# EEPROM.net
KiCad netlist of a schematic drawn in Altium Designer
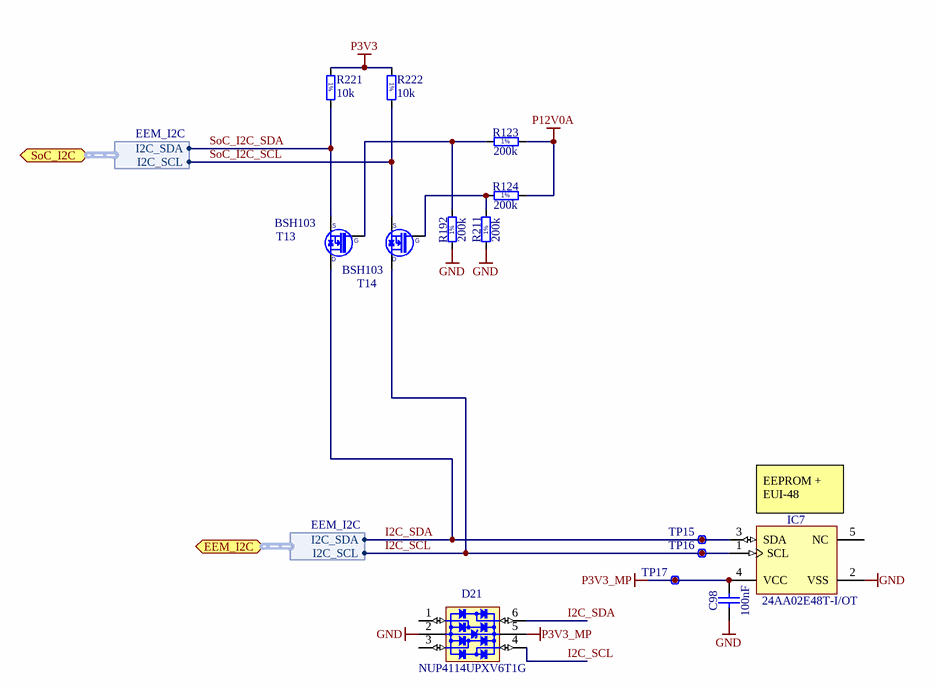
[diagram p0: EEPROM.SchDoc]

(export (version "E")
  (design (tool "Eeschema 10.0.6"))
  (components
    (comp (ref "C98")
      (value "100nF")
      (footprint "CAPC1005X55N")
      (description "Non-polarised capacitor")
      (fields
        (field (name "PART NUMBER") "CC0402_100NF_16V_10%_X5R")
        (field (name "VOLTAGE") "16V")
        (field (name "AUTHOR") "CERN DEM JLC")
      )
      (libsource (lib "Capacitors") (part "Capacitor - non polarized"))
    )
    (comp (ref "D21")
      (value "NUP4114UPXV6T1G")
      (footprint "SOTFL50P160X60-6N")
      (fields
        (field (name "VOLTAGE") "5.5V")
        (field (name "MANUFACTURER") "ON SEMICONDUCTOR")
        (field (name "AUTHOR") "CERN DEM JLC")
      )
      (libsource (lib "ICs And Semiconductors") (part "NUP4114"))
    )
    (comp (ref "IC7")
      (value "24AA02E48T-I/OT")
      (footprint "SOT95P280X145-5N")
      (description "1.7V-5.5V, 2K I2C Serial EEPROM With EUI-48 Node Identity")
      (fields (field (name "MANUFACTURER") "MICROCHIP TECHNOLOGY") (field (name "AUTHOR") "CERN DEM MR"))
      (libsource (lib "ICs And Semiconductors") (part "24AA02E48T-I/OT"))
    )
    (comp (ref "R123")
      (value "200k")
      (footprint "RESC1005X40N")
      (description "Resistor - 1%")
      (fields
        (field (name "PART NUMBER") "R0402_200K_1%_0.0625W_100PPM")
        (field (name "POWER") "0.0625W")
        (field (name "AUTHOR") "CERN DEM JLC")
      )
      (libsource (lib "Resistors") (part "Resistor - 1%"))
    )
    (comp (ref "R124")
      (value "200k")
      (footprint "RESC1005X40N")
      (description "Resistor - 1%")
      (fields
        (field (name "PART NUMBER") "R0402_200K_1%_0.0625W_100PPM")
        (field (name "POWER") "0.0625W")
        (field (name "AUTHOR") "CERN DEM JLC")
      )
      (libsource (lib "Resistors") (part "Resistor - 1%"))
    )
    (comp (ref "R192")
      (value "200k")
      (footprint "RESC1005X40N")
      (description "Resistor - 1%")
      (fields
        (field (name "PART NUMBER") "R0402_200K_1%_0.0625W_100PPM")
        (field (name "POWER") "0.0625W")
        (field (name "AUTHOR") "CERN DEM JLC")
      )
      (libsource (lib "Resistors") (part "Resistor - 1%"))
    )
    (comp (ref "R211")
      (value "200k")
      (footprint "RESC1005X40N")
      (description "Resistor - 1%")
      (fields
        (field (name "PART NUMBER") "R0402_200K_1%_0.0625W_100PPM")
        (field (name "POWER") "0.0625W")
        (field (name "AUTHOR") "CERN DEM JLC")
      )
      (libsource (lib "Resistors") (part "Resistor - 1%"))
    )
    (comp (ref "R221")
      (value "10k")
      (footprint "RESC1005X40N")
      (description "Resistor - 1%")
      (fields
        (field (name "PART NUMBER") "R0402_10K_1%_0.0625W_100PPM")
        (field (name "POWER") "0.0625W")
        (field (name "AUTHOR") "CERN DEM JLC")
      )
      (libsource (lib "Resistors") (part "Resistor - 1%"))
    )
    (comp (ref "R222")
      (value "10k")
      (footprint "RESC1005X40N")
      (description "Resistor - 1%")
      (fields
        (field (name "PART NUMBER") "R0402_10K_1%_0.0625W_100PPM")
        (field (name "POWER") "0.0625W")
        (field (name "AUTHOR") "CERN DEM JLC")
      )
      (libsource (lib "Resistors") (part "Resistor - 1%"))
    )
    (comp (ref "T13")
      (value "BSH103")
      (footprint "SOT95P230X110-3N")
      (description "N-CHANNEL MOSFET WITH DIODE")
      (fields (field (name "MANUFACTURER") "NEXPERIA") (field (name "AUTHOR") "CERN DEM JLC"))
      (libsource (lib "ICs And Semiconductors") (part "N-MOSFET-D 1G 2S 3D"))
    )
    (comp (ref "T14")
      (value "BSH103")
      (footprint "SOT95P230X110-3N")
      (description "N-CHANNEL MOSFET WITH DIODE")
      (fields (field (name "MANUFACTURER") "NEXPERIA") (field (name "AUTHOR") "CERN DEM JLC"))
      (libsource (lib "ICs And Semiconductors") (part "N-MOSFET-D 1G 2S 3D"))
    )
    (comp (ref "TP15")
      (value "Test Point")
      (footprint "TPS127")
      (fields (field (name "PART NUMBER") "SMD_PAD_1.27X1.27MM") (field (name "AUTHOR") "CERN DEM JLC"))
      (libsource (lib "Eletro-mechanical") (part "Test Point"))
    )
    (comp (ref "TP16")
      (value "Test Point")
      (footprint "TPS127")
      (fields (field (name "PART NUMBER") "SMD_PAD_1.27X1.27MM") (field (name "AUTHOR") "CERN DEM JLC"))
      (libsource (lib "Eletro-mechanical") (part "Test Point"))
    )
    (comp (ref "TP17")
      (value "Test Point")
      (footprint "TPS127")
      (fields (field (name "PART NUMBER") "SMD_PAD_1.27X1.27MM") (field (name "AUTHOR") "CERN DEM JLC"))
      (libsource (lib "Eletro-mechanical") (part "Test Point"))
    )
  )
  (nets
    (net (code "2") (name "/I2C_SCL") (class "Default")
      (node (ref "D21") (pin "4") (pinfunction "I/O3_4") (pintype "bidirectional"))
      (node (ref "IC7") (pin "1") (pinfunction "SCL_1") (pintype "input"))
      (node (ref "T14") (pin "3") (pinfunction "D_3") (pintype "passive"))
      (node (ref "TP16") (pin "1") (pinfunction "1_1") (pintype "bidirectional"))
    )
    (net (code "3") (name "/I2C_SDA") (class "Default")
      (node (ref "D21") (pin "6") (pinfunction "I/O4_6") (pintype "bidirectional"))
      (node (ref "IC7") (pin "3") (pinfunction "SDA_3") (pintype "bidirectional"))
      (node (ref "T13") (pin "3") (pinfunction "D_3") (pintype "passive"))
      (node (ref "TP15") (pin "1") (pinfunction "1_1") (pintype "bidirectional"))
    )
    (net (code "4") (name "/SoC_I2C_SCL") (class "Default")
      (node (ref "R222") (pin "2") (pinfunction "2_2") (pintype "passive"))
      (node (ref "T14") (pin "2") (pinfunction "S_2") (pintype "passive"))
    )
    (net (code "5") (name "/SoC_I2C_SDA") (class "Default")
      (node (ref "R221") (pin "2") (pinfunction "2_2") (pintype "passive"))
      (node (ref "T13") (pin "2") (pinfunction "S_2") (pintype "passive"))
    )
    (net (code "7") (name "GND") (class "Default")
      (node (ref "C98") (pin "1") (pinfunction "1_1") (pintype "passive"))
      (node (ref "D21") (pin "2") (pinfunction "GND_2") (pintype "power_in"))
      (node (ref "IC7") (pin "2") (pinfunction "VSS_2") (pintype "power_in"))
      (node (ref "R192") (pin "1") (pinfunction "1_1") (pintype "passive"))
      (node (ref "R211") (pin "1") (pinfunction "1_1") (pintype "passive"))
    )
    (net (code "8") (name "Net-(T13-G)") (class "Default")
      (node (ref "R123") (pin "1") (pinfunction "1_1") (pintype "passive"))
      (node (ref "R192") (pin "2") (pinfunction "2_2") (pintype "passive"))
      (node (ref "T13") (pin "1") (pinfunction "G_1") (pintype "passive"))
    )
    (net (code "9") (name "Net-(T14-G)") (class "Default")
      (node (ref "R124") (pin "1") (pinfunction "1_1") (pintype "passive"))
      (node (ref "R211") (pin "2") (pinfunction "2_2") (pintype "passive"))
      (node (ref "T14") (pin "1") (pinfunction "G_1") (pintype "passive"))
    )
    (net (code "10") (name "P3V3") (class "Default")
      (node (ref "R221") (pin "1") (pinfunction "1_1") (pintype "passive"))
      (node (ref "R222") (pin "1") (pinfunction "1_1") (pintype "passive"))
    )
    (net (code "11") (name "P3V3_MP") (class "Default")
      (node (ref "C98") (pin "2") (pinfunction "2_2") (pintype "passive"))
      (node (ref "D21") (pin "5") (pinfunction "VBUS_5") (pintype "power_in"))
      (node (ref "IC7") (pin "4") (pinfunction "VCC_4") (pintype "power_in"))
      (node (ref "TP17") (pin "1") (pinfunction "1_1") (pintype "bidirectional"))
    )
    (net (code "12") (name "P12V0A") (class "Default")
      (node (ref "R123") (pin "2") (pinfunction "2_2") (pintype "passive"))
      (node (ref "R124") (pin "2") (pinfunction "2_2") (pintype "passive"))
    )
    (net (code "13") (name "unconnected-(D21-I{slash}O1-Pad1)") (class "Default")
      (node (ref "D21") (pin "1") (pinfunction "I/O1_1") (pintype "bidirectional"))
    )
    (net (code "14") (name "unconnected-(D21-I{slash}O2-Pad3)") (class "Default")
      (node (ref "D21") (pin "3") (pinfunction "I/O2_3") (pintype "bidirectional"))
    )
    (net (code "15") (name "unconnected-(IC7-NC-Pad5)") (class "Default")
      (node (ref "IC7") (pin "5") (pinfunction "NC_5") (pintype "passive"))
    )
  )
)
